# HBridge84.net
KiCad netlist of a schematic drawn in EAGLE
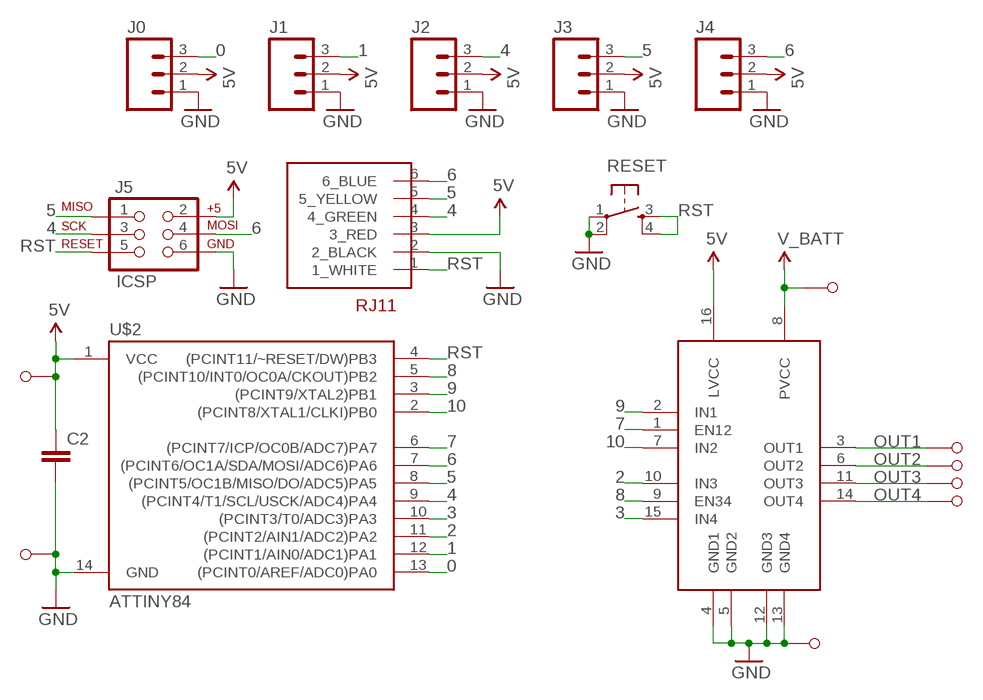
[diagram p0: schematic, sheet 1]

(export (version "E")
  (design (tool "Eeschema 10.0.6"))
  (components
    (comp (ref "C2")
      (value "CAPPTH")
      (footprint "eagle-import:CAP-PTH-SMALL")
      (libsource (lib "eagle-import") (part "CAPPTH"))
    )
    (comp (ref "J0")
      (value "M03PTH")
      (footprint "eagle-import:1X03")
      (libsource (lib "eagle-import") (part "M03PTH"))
    )
    (comp (ref "J1")
      (value "M03PTH")
      (footprint "eagle-import:1X03")
      (libsource (lib "eagle-import") (part "M03PTH"))
    )
    (comp (ref "J2")
      (value "M03PTH")
      (footprint "eagle-import:1X03")
      (libsource (lib "eagle-import") (part "M03PTH"))
    )
    (comp (ref "J3")
      (value "M03PTH")
      (footprint "eagle-import:1X03")
      (libsource (lib "eagle-import") (part "M03PTH"))
    )
    (comp (ref "J4")
      (value "M03PTH")
      (footprint "eagle-import:1X03")
      (libsource (lib "eagle-import") (part "M03PTH"))
    )
    (comp (ref "J5")
      (value "ICSP")
      (footprint "eagle-import:2X3-NS")
      (libsource (lib "eagle-import") (part "AVR_SPI_PRG_6LABELED"))
    )
    (comp (ref "RESET")
      (value "TAC_SWITCHPTH")
      (footprint "eagle-import:TACTILE-PTH")
      (libsource (lib "eagle-import") (part "TAC_SWITCHPTH"))
    )
    (comp (ref "SN754410")
      (value "SN754410")
      (footprint "eagle-import:DIP16")
      (libsource (lib "eagle-import") (part "SN754410"))
    )
    (comp (ref "U$1")
      (value "M1")
      (footprint "eagle-import:M1_NO_STRAIN")
      (libsource (lib "eagle-import") (part "M1"))
    )
    (comp (ref "U$2")
      (value "ATTINY84")
      (footprint "eagle-import:DIL14")
      (libsource (lib "eagle-import") (part "ATTINY84ATTINY84-20PU"))
    )
    (comp (ref "U$3")
      (value "M1")
      (footprint "eagle-import:M1_NO_STRAIN")
      (libsource (lib "eagle-import") (part "M1"))
    )
    (comp (ref "U$4")
      (value "M1")
      (footprint "eagle-import:M1_NO_STRAIN")
      (libsource (lib "eagle-import") (part "M1"))
    )
    (comp (ref "U$5")
      (value "M1")
      (footprint "eagle-import:M1_NO_STRAIN")
      (libsource (lib "eagle-import") (part "M1"))
    )
    (comp (ref "U$6")
      (value "M1")
      (footprint "eagle-import:M1_NO_STRAIN")
      (libsource (lib "eagle-import") (part "M1"))
    )
    (comp (ref "U$7")
      (value "RJ12")
      (footprint "eagle-import:RJ12")
      (libsource (lib "eagle-import") (part "RJ12"))
    )
    (comp (ref "U$8")
      (value "M1")
      (footprint "eagle-import:M1_NO_STRAIN")
      (libsource (lib "eagle-import") (part "M1"))
    )
    (comp (ref "U$9")
      (value "M1")
      (footprint "eagle-import:M1_NO_STRAIN")
      (libsource (lib "eagle-import") (part "M1"))
    )
    (comp (ref "U$10")
      (value "M1")
      (footprint "eagle-import:M1_NO_STRAIN")
      (libsource (lib "eagle-import") (part "M1"))
    )
  )
  (nets
    (net (code "1") (name "/0") (class "Default")
      (node (ref "J0") (pin "3") (pinfunction "3_3") (pintype "passive"))
      (node (ref "U$2") (pin "13") (pinfunction "(PCINT0/AREF/ADC0)PA0_13") (pintype "bidirectional"))
    )
    (net (code "2") (name "/1") (class "Default")
      (node (ref "J1") (pin "3") (pinfunction "3_3") (pintype "passive"))
      (node (ref "U$2") (pin "12") (pinfunction "(PCINT1/AIN0/ADC1)PA1_12") (pintype "bidirectional"))
    )
    (net (code "3") (name "/2") (class "Default")
      (node (ref "SN754410") (pin "10") (pinfunction "IN3_10") (pintype "bidirectional"))
      (node (ref "U$2") (pin "11") (pinfunction "(PCINT2/AIN1/ADC2)PA2_11") (pintype "bidirectional"))
    )
    (net (code "4") (name "/3") (class "Default")
      (node (ref "SN754410") (pin "15") (pinfunction "IN4_15") (pintype "bidirectional"))
      (node (ref "U$2") (pin "10") (pinfunction "(PCINT3/T0/ADC3)PA3_10") (pintype "bidirectional"))
    )
    (net (code "5") (name "/4") (class "Default")
      (node (ref "J2") (pin "3") (pinfunction "3_3") (pintype "passive"))
      (node (ref "J5") (pin "3") (pinfunction "SCK_3") (pintype "passive"))
      (node (ref "U$2") (pin "9") (pinfunction "(PCINT4/T1/SCL/USCK/ADC4)PA4_9") (pintype "bidirectional"))
      (node (ref "U$7") (pin "4") (pinfunction "4_GREEN_4") (pintype "bidirectional"))
    )
    (net (code "6") (name "/5") (class "Default")
      (node (ref "J3") (pin "3") (pinfunction "3_3") (pintype "passive"))
      (node (ref "J5") (pin "1") (pinfunction "MISO_1") (pintype "passive"))
      (node (ref "U$2") (pin "8") (pinfunction "(PCINT5/OC1B/MISO/DO/ADC5)PA5_8") (pintype "bidirectional"))
      (node (ref "U$7") (pin "5") (pinfunction "5_YELLOW_5") (pintype "bidirectional"))
    )
    (net (code "7") (name "/6") (class "Default")
      (node (ref "J4") (pin "3") (pinfunction "3_3") (pintype "passive"))
      (node (ref "J5") (pin "4") (pinfunction "MOSI_4") (pintype "passive"))
      (node (ref "U$2") (pin "7") (pinfunction "(PCINT6/OC1A/SDA/MOSI/ADC6)PA6_7") (pintype "bidirectional"))
      (node (ref "U$7") (pin "6") (pinfunction "6_BLUE_6") (pintype "bidirectional"))
    )
    (net (code "8") (name "/7") (class "Default")
      (node (ref "SN754410") (pin "1") (pinfunction "EN12_1") (pintype "bidirectional"))
      (node (ref "U$2") (pin "6") (pinfunction "(PCINT7/ICP/OC0B/ADC7)PA7_6") (pintype "bidirectional"))
    )
    (net (code "9") (name "/8") (class "Default")
      (node (ref "SN754410") (pin "9") (pinfunction "EN34_9") (pintype "bidirectional"))
      (node (ref "U$2") (pin "5") (pinfunction "(PCINT10/INT0/OC0A/CKOUT)PB2_5") (pintype "bidirectional"))
    )
    (net (code "10") (name "/9") (class "Default")
      (node (ref "SN754410") (pin "2") (pinfunction "IN1_2") (pintype "bidirectional"))
      (node (ref "U$2") (pin "3") (pinfunction "(PCINT9/XTAL2)PB1_3") (pintype "bidirectional"))
    )
    (net (code "11") (name "/10") (class "Default")
      (node (ref "SN754410") (pin "7") (pinfunction "IN2_7") (pintype "bidirectional"))
      (node (ref "U$2") (pin "2") (pinfunction "(PCINT8/XTAL1/CLKI)PB0_2") (pintype "bidirectional"))
    )
    (net (code "12") (name "/OUT1") (class "Default")
      (node (ref "SN754410") (pin "3") (pinfunction "OUT1_3") (pintype "bidirectional"))
      (node (ref "U$1") (pin "P$1") (pinfunction "P$1_P$1") (pintype "bidirectional"))
    )
    (net (code "13") (name "/OUT2") (class "Default")
      (node (ref "SN754410") (pin "6") (pinfunction "OUT2_6") (pintype "bidirectional"))
      (node (ref "U$3") (pin "P$1") (pinfunction "P$1_P$1") (pintype "bidirectional"))
    )
    (net (code "14") (name "/OUT3") (class "Default")
      (node (ref "SN754410") (pin "11") (pinfunction "OUT3_11") (pintype "bidirectional"))
      (node (ref "U$4") (pin "P$1") (pinfunction "P$1_P$1") (pintype "bidirectional"))
    )
    (net (code "15") (name "/OUT4") (class "Default")
      (node (ref "SN754410") (pin "14") (pinfunction "OUT4_14") (pintype "bidirectional"))
      (node (ref "U$5") (pin "P$1") (pinfunction "P$1_P$1") (pintype "bidirectional"))
    )
    (net (code "16") (name "/RST") (class "Default")
      (node (ref "J5") (pin "5") (pinfunction "RST_5") (pintype "passive"))
      (node (ref "RESET") (pin "3") (pinfunction "3_3") (pintype "passive"))
      (node (ref "RESET") (pin "4") (pinfunction "4_4") (pintype "passive"))
      (node (ref "U$2") (pin "4") (pinfunction "(PCINT11/~{RESET/DW})PB3_4") (pintype "bidirectional"))
      (node (ref "U$7") (pin "1") (pinfunction "1_WHITE_1") (pintype "bidirectional"))
    )
    (net (code "17") (name "5V") (class "Default")
      (node (ref "C2") (pin "1") (pinfunction "1_1") (pintype "passive"))
      (node (ref "J0") (pin "2") (pinfunction "2_2") (pintype "passive"))
      (node (ref "J1") (pin "2") (pinfunction "2_2") (pintype "passive"))
      (node (ref "J2") (pin "2") (pinfunction "2_2") (pintype "passive"))
      (node (ref "J3") (pin "2") (pinfunction "2_2") (pintype "passive"))
      (node (ref "J4") (pin "2") (pinfunction "2_2") (pintype "passive"))
      (node (ref "J5") (pin "2") (pinfunction "V+_2") (pintype "passive"))
      (node (ref "SN754410") (pin "16") (pinfunction "LVCC_16") (pintype "bidirectional"))
      (node (ref "U$10") (pin "P$1") (pinfunction "P$1_P$1") (pintype "bidirectional"))
      (node (ref "U$2") (pin "1") (pinfunction "VCC_1") (pintype "bidirectional"))
      (node (ref "U$7") (pin "3") (pinfunction "3_RED_3") (pintype "bidirectional"))
    )
    (net (code "18") (name "GND") (class "Default")
      (node (ref "C2") (pin "2") (pinfunction "2_2") (pintype "passive"))
      (node (ref "J0") (pin "1") (pinfunction "1_1") (pintype "passive"))
      (node (ref "J1") (pin "1") (pinfunction "1_1") (pintype "passive"))
      (node (ref "J2") (pin "1") (pinfunction "1_1") (pintype "passive"))
      (node (ref "J3") (pin "1") (pinfunction "1_1") (pintype "passive"))
      (node (ref "J4") (pin "1") (pinfunction "1_1") (pintype "passive"))
      (node (ref "J5") (pin "6") (pinfunction "GND_6") (pintype "passive"))
      (node (ref "RESET") (pin "1") (pinfunction "1_1") (pintype "passive"))
      (node (ref "RESET") (pin "2") (pinfunction "2_2") (pintype "passive"))
      (node (ref "SN754410") (pin "12") (pinfunction "GND3_12") (pintype "bidirectional"))
      (node (ref "SN754410") (pin "13") (pinfunction "GND4_13") (pintype "bidirectional"))
      (node (ref "SN754410") (pin "4") (pinfunction "GND1_4") (pintype "bidirectional"))
      (node (ref "SN754410") (pin "5") (pinfunction "GND2_5") (pintype "bidirectional"))
      (node (ref "U$2") (pin "14") (pinfunction "GND_14") (pintype "bidirectional"))
      (node (ref "U$7") (pin "2") (pinfunction "2_BLACK_2") (pintype "bidirectional"))
      (node (ref "U$8") (pin "P$1") (pinfunction "P$1_P$1") (pintype "bidirectional"))
      (node (ref "U$9") (pin "P$1") (pinfunction "P$1_P$1") (pintype "bidirectional"))
    )
    (net (code "19") (name "V_BATT") (class "Default")
      (node (ref "SN754410") (pin "8") (pinfunction "PVCC_8") (pintype "bidirectional"))
      (node (ref "U$6") (pin "P$1") (pinfunction "P$1_P$1") (pintype "bidirectional"))
    )
  )
)
